# KeyBoard.net
KiCad netlist of a schematic drawn in EAGLE
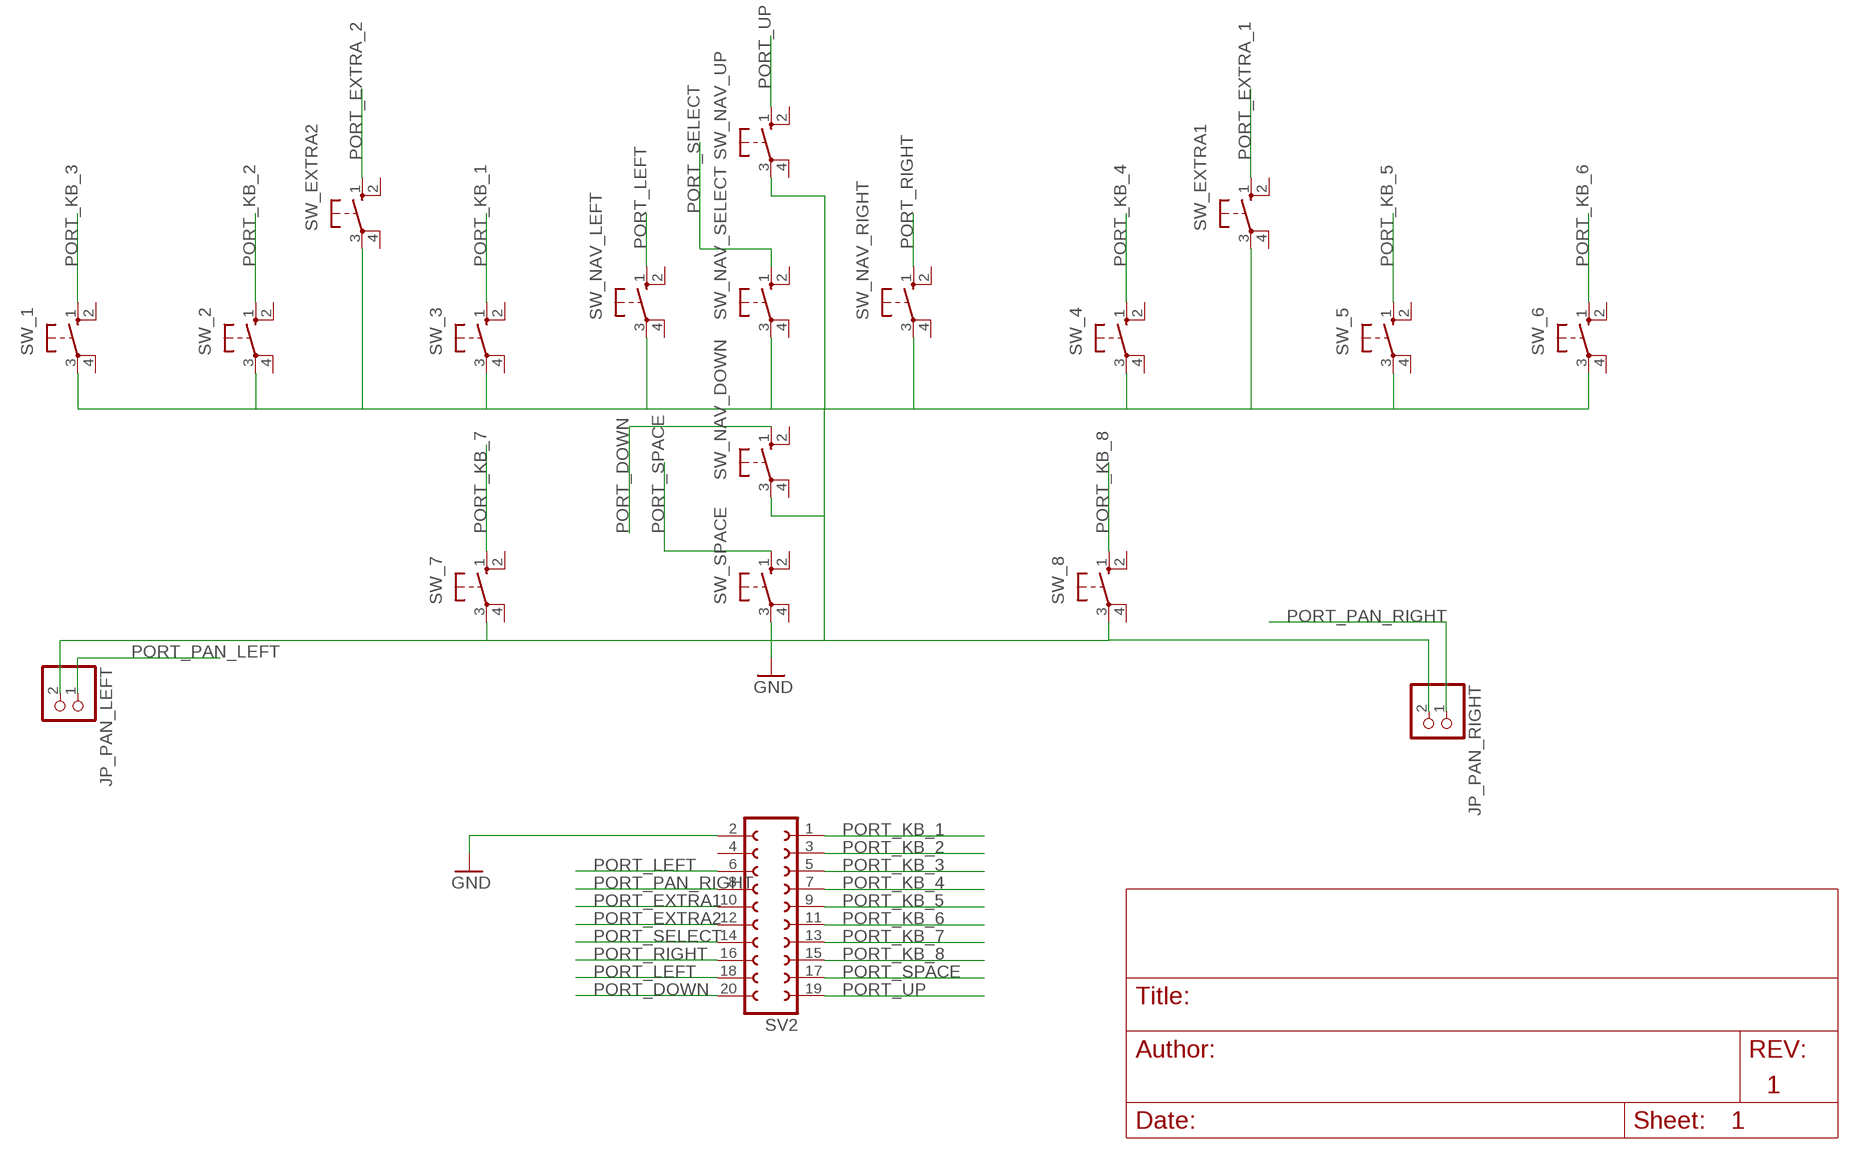
[diagram p0: schematic, sheet 1]

(export (version "E")
  (design (tool "Eeschema 10.0.6"))
  (components
    (comp (ref "JP_PAN_LEFT")
      (value "PINHD-1X2")
      (footprint "eagle-import:1X02")
      (libsource (lib "eagle-import") (part "PINHD-1X2"))
    )
    (comp (ref "JP_PAN_RIGHT")
      (value "PINHD-1X2")
      (footprint "eagle-import:1X02")
      (libsource (lib "eagle-import") (part "PINHD-1X2"))
    )
    (comp (ref "SV2")
      (value "FE10-2")
      (footprint "eagle-import:FE10-2")
      (libsource (lib "eagle-import") (part "FE10-2"))
    )
    (comp (ref "SW_1")
      (value "10-XX")
      (footprint "eagle-import:B3F-10XX")
      (fields (field (name "MPN") "B3F-1000"))
      (libsource (lib "eagle-import") (part "10-XX"))
    )
    (comp (ref "SW_2")
      (value "10-XX")
      (footprint "eagle-import:B3F-10XX")
      (fields (field (name "MPN") "B3F-1000"))
      (libsource (lib "eagle-import") (part "10-XX"))
    )
    (comp (ref "SW_3")
      (value "10-XX")
      (footprint "eagle-import:B3F-10XX")
      (fields (field (name "MPN") "B3F-1000"))
      (libsource (lib "eagle-import") (part "10-XX"))
    )
    (comp (ref "SW_4")
      (value "10-XX")
      (footprint "eagle-import:B3F-10XX")
      (fields (field (name "MPN") "B3F-1000"))
      (libsource (lib "eagle-import") (part "10-XX"))
    )
    (comp (ref "SW_5")
      (value "10-XX")
      (footprint "eagle-import:B3F-10XX")
      (fields (field (name "MPN") "B3F-1000"))
      (libsource (lib "eagle-import") (part "10-XX"))
    )
    (comp (ref "SW_6")
      (value "10-XX")
      (footprint "eagle-import:B3F-10XX")
      (fields (field (name "MPN") "B3F-1000"))
      (libsource (lib "eagle-import") (part "10-XX"))
    )
    (comp (ref "SW_7")
      (value "10-XX")
      (footprint "eagle-import:B3F-10XX")
      (fields (field (name "MPN") "B3F-1000"))
      (libsource (lib "eagle-import") (part "10-XX"))
    )
    (comp (ref "SW_8")
      (value "10-XX")
      (footprint "eagle-import:B3F-10XX")
      (fields (field (name "MPN") "B3F-1000"))
      (libsource (lib "eagle-import") (part "10-XX"))
    )
    (comp (ref "SW_EXTRA1")
      (value "10-XX")
      (footprint "eagle-import:B3F-10XX")
      (fields (field (name "MPN") "B3F-1000"))
      (libsource (lib "eagle-import") (part "10-XX"))
    )
    (comp (ref "SW_EXTRA2")
      (value "10-XX")
      (footprint "eagle-import:B3F-10XX")
      (fields (field (name "MPN") "B3F-1000"))
      (libsource (lib "eagle-import") (part "10-XX"))
    )
    (comp (ref "SW_NAV_DOWN")
      (value "10-XX")
      (footprint "eagle-import:B3F-10XX")
      (fields (field (name "MPN") "B3F-1000"))
      (libsource (lib "eagle-import") (part "10-XX"))
    )
    (comp (ref "SW_NAV_LEFT")
      (value "10-XX")
      (footprint "eagle-import:B3F-10XX")
      (fields (field (name "MPN") "B3F-1000"))
      (libsource (lib "eagle-import") (part "10-XX"))
    )
    (comp (ref "SW_NAV_RIGHT")
      (value "10-XX")
      (footprint "eagle-import:B3F-10XX")
      (fields (field (name "MPN") "B3F-1000"))
      (libsource (lib "eagle-import") (part "10-XX"))
    )
    (comp (ref "SW_NAV_SELECT")
      (value "10-XX")
      (footprint "eagle-import:B3F-10XX")
      (fields (field (name "MPN") "B3F-1000"))
      (libsource (lib "eagle-import") (part "10-XX"))
    )
    (comp (ref "SW_NAV_UP")
      (value "10-XX")
      (footprint "eagle-import:B3F-10XX")
      (fields (field (name "MPN") "B3F-1000"))
      (libsource (lib "eagle-import") (part "10-XX"))
    )
    (comp (ref "SW_SPACE")
      (value "10-XX")
      (footprint "eagle-import:B3F-10XX")
      (fields (field (name "MPN") "B3F-1000"))
      (libsource (lib "eagle-import") (part "10-XX"))
    )
  )
  (nets
    (net (code "1") (name "/PORT_DOWN") (class "Default")
      (node (ref "SV2") (pin "20") (pinfunction "20_20") (pintype "passive"))
      (node (ref "SW_NAV_DOWN") (pin "1") (pinfunction "S_1") (pintype "passive"))
    )
    (net (code "2") (name "/PORT_EXTRA1") (class "Default")
      (node (ref "SV2") (pin "10") (pinfunction "10_10") (pintype "passive"))
    )
    (net (code "3") (name "/PORT_EXTRA2") (class "Default")
      (node (ref "SV2") (pin "12") (pinfunction "12_12") (pintype "passive"))
    )
    (net (code "4") (name "/PORT_EXTRA_1") (class "Default")
      (node (ref "SW_EXTRA1") (pin "1") (pinfunction "S_1") (pintype "passive"))
    )
    (net (code "5") (name "/PORT_EXTRA_2") (class "Default")
      (node (ref "SW_EXTRA2") (pin "1") (pinfunction "S_1") (pintype "passive"))
    )
    (net (code "6") (name "/PORT_KB_1") (class "Default")
      (node (ref "SV2") (pin "1") (pinfunction "1_1") (pintype "passive"))
      (node (ref "SW_3") (pin "1") (pinfunction "S_1") (pintype "passive"))
    )
    (net (code "7") (name "/PORT_KB_2") (class "Default")
      (node (ref "SV2") (pin "3") (pinfunction "3_3") (pintype "passive"))
      (node (ref "SW_2") (pin "1") (pinfunction "S_1") (pintype "passive"))
    )
    (net (code "8") (name "/PORT_KB_3") (class "Default")
      (node (ref "SV2") (pin "5") (pinfunction "5_5") (pintype "passive"))
      (node (ref "SW_1") (pin "1") (pinfunction "S_1") (pintype "passive"))
    )
    (net (code "9") (name "/PORT_KB_4") (class "Default")
      (node (ref "SV2") (pin "7") (pinfunction "7_7") (pintype "passive"))
      (node (ref "SW_4") (pin "1") (pinfunction "S_1") (pintype "passive"))
    )
    (net (code "10") (name "/PORT_KB_5") (class "Default")
      (node (ref "SV2") (pin "9") (pinfunction "9_9") (pintype "passive"))
      (node (ref "SW_5") (pin "1") (pinfunction "S_1") (pintype "passive"))
    )
    (net (code "11") (name "/PORT_KB_6") (class "Default")
      (node (ref "SV2") (pin "11") (pinfunction "11_11") (pintype "passive"))
      (node (ref "SW_6") (pin "1") (pinfunction "S_1") (pintype "passive"))
    )
    (net (code "12") (name "/PORT_KB_7") (class "Default")
      (node (ref "SV2") (pin "13") (pinfunction "13_13") (pintype "passive"))
      (node (ref "SW_7") (pin "1") (pinfunction "S_1") (pintype "passive"))
    )
    (net (code "13") (name "/PORT_KB_8") (class "Default")
      (node (ref "SV2") (pin "15") (pinfunction "15_15") (pintype "passive"))
      (node (ref "SW_8") (pin "1") (pinfunction "S_1") (pintype "passive"))
    )
    (net (code "14") (name "/PORT_LEFT") (class "Default")
      (node (ref "SV2") (pin "18") (pinfunction "18_18") (pintype "passive"))
      (node (ref "SV2") (pin "6") (pinfunction "6_6") (pintype "passive"))
      (node (ref "SW_NAV_LEFT") (pin "1") (pinfunction "S_1") (pintype "passive"))
    )
    (net (code "15") (name "/PORT_PAN_LEFT") (class "Default")
      (node (ref "JP_PAN_LEFT") (pin "1") (pinfunction "1_1") (pintype "passive"))
    )
    (net (code "16") (name "/PORT_PAN_RIGHT") (class "Default")
      (node (ref "JP_PAN_RIGHT") (pin "1") (pinfunction "1_1") (pintype "passive"))
      (node (ref "SV2") (pin "8") (pinfunction "8_8") (pintype "passive"))
    )
    (net (code "17") (name "/PORT_RIGHT") (class "Default")
      (node (ref "SV2") (pin "16") (pinfunction "16_16") (pintype "passive"))
      (node (ref "SW_NAV_RIGHT") (pin "1") (pinfunction "S_1") (pintype "passive"))
    )
    (net (code "18") (name "/PORT_SELECT") (class "Default")
      (node (ref "SV2") (pin "14") (pinfunction "14_14") (pintype "passive"))
      (node (ref "SW_NAV_SELECT") (pin "1") (pinfunction "S_1") (pintype "passive"))
    )
    (net (code "19") (name "/PORT_SPACE") (class "Default")
      (node (ref "SV2") (pin "17") (pinfunction "17_17") (pintype "passive"))
      (node (ref "SW_SPACE") (pin "1") (pinfunction "S_1") (pintype "passive"))
    )
    (net (code "20") (name "/PORT_UP") (class "Default")
      (node (ref "SV2") (pin "19") (pinfunction "19_19") (pintype "passive"))
      (node (ref "SW_NAV_UP") (pin "1") (pinfunction "S_1") (pintype "passive"))
    )
    (net (code "21") (name "GND") (class "Default")
      (node (ref "JP_PAN_LEFT") (pin "2") (pinfunction "2_2") (pintype "passive"))
      (node (ref "JP_PAN_RIGHT") (pin "2") (pinfunction "2_2") (pintype "passive"))
      (node (ref "SV2") (pin "2") (pinfunction "2_2") (pintype "passive"))
      (node (ref "SW_1") (pin "3") (pinfunction "P_3") (pintype "passive"))
      (node (ref "SW_2") (pin "3") (pinfunction "P_3") (pintype "passive"))
      (node (ref "SW_3") (pin "3") (pinfunction "P_3") (pintype "passive"))
      (node (ref "SW_4") (pin "3") (pinfunction "P_3") (pintype "passive"))
      (node (ref "SW_5") (pin "3") (pinfunction "P_3") (pintype "passive"))
      (node (ref "SW_6") (pin "3") (pinfunction "P_3") (pintype "passive"))
      (node (ref "SW_7") (pin "3") (pinfunction "P_3") (pintype "passive"))
      (node (ref "SW_8") (pin "3") (pinfunction "P_3") (pintype "passive"))
      (node (ref "SW_EXTRA1") (pin "3") (pinfunction "P_3") (pintype "passive"))
      (node (ref "SW_EXTRA2") (pin "3") (pinfunction "P_3") (pintype "passive"))
      (node (ref "SW_NAV_DOWN") (pin "3") (pinfunction "P_3") (pintype "passive"))
      (node (ref "SW_NAV_LEFT") (pin "3") (pinfunction "P_3") (pintype "passive"))
      (node (ref "SW_NAV_RIGHT") (pin "3") (pinfunction "P_3") (pintype "passive"))
      (node (ref "SW_NAV_SELECT") (pin "3") (pinfunction "P_3") (pintype "passive"))
      (node (ref "SW_NAV_UP") (pin "3") (pinfunction "P_3") (pintype "passive"))
      (node (ref "SW_SPACE") (pin "3") (pinfunction "P_3") (pintype "passive"))
    )
    (net (code "22") (name "unconnected-(SV2-Pad4)") (class "Default")
      (node (ref "SV2") (pin "4") (pinfunction "4_4") (pintype "passive"))
    )
    (net (code "23") (name "unconnected-(SW_1-P1-Pad4)") (class "Default")
      (node (ref "SW_1") (pin "4") (pinfunction "P1_4") (pintype "passive"))
    )
    (net (code "24") (name "unconnected-(SW_1-S1-Pad2)") (class "Default")
      (node (ref "SW_1") (pin "2") (pinfunction "S1_2") (pintype "passive"))
    )
    (net (code "25") (name "unconnected-(SW_2-P1-Pad4)") (class "Default")
      (node (ref "SW_2") (pin "4") (pinfunction "P1_4") (pintype "passive"))
    )
    (net (code "26") (name "unconnected-(SW_2-S1-Pad2)") (class "Default")
      (node (ref "SW_2") (pin "2") (pinfunction "S1_2") (pintype "passive"))
    )
    (net (code "27") (name "unconnected-(SW_3-P1-Pad4)") (class "Default")
      (node (ref "SW_3") (pin "4") (pinfunction "P1_4") (pintype "passive"))
    )
    (net (code "28") (name "unconnected-(SW_3-S1-Pad2)") (class "Default")
      (node (ref "SW_3") (pin "2") (pinfunction "S1_2") (pintype "passive"))
    )
    (net (code "29") (name "unconnected-(SW_4-P1-Pad4)") (class "Default")
      (node (ref "SW_4") (pin "4") (pinfunction "P1_4") (pintype "passive"))
    )
    (net (code "30") (name "unconnected-(SW_4-S1-Pad2)") (class "Default")
      (node (ref "SW_4") (pin "2") (pinfunction "S1_2") (pintype "passive"))
    )
    (net (code "31") (name "unconnected-(SW_5-P1-Pad4)") (class "Default")
      (node (ref "SW_5") (pin "4") (pinfunction "P1_4") (pintype "passive"))
    )
    (net (code "32") (name "unconnected-(SW_5-S1-Pad2)") (class "Default")
      (node (ref "SW_5") (pin "2") (pinfunction "S1_2") (pintype "passive"))
    )
    (net (code "33") (name "unconnected-(SW_6-P1-Pad4)") (class "Default")
      (node (ref "SW_6") (pin "4") (pinfunction "P1_4") (pintype "passive"))
    )
    (net (code "34") (name "unconnected-(SW_6-S1-Pad2)") (class "Default")
      (node (ref "SW_6") (pin "2") (pinfunction "S1_2") (pintype "passive"))
    )
    (net (code "35") (name "unconnected-(SW_7-P1-Pad4)") (class "Default")
      (node (ref "SW_7") (pin "4") (pinfunction "P1_4") (pintype "passive"))
    )
    (net (code "36") (name "unconnected-(SW_7-S1-Pad2)") (class "Default")
      (node (ref "SW_7") (pin "2") (pinfunction "S1_2") (pintype "passive"))
    )
    (net (code "37") (name "unconnected-(SW_8-P1-Pad4)") (class "Default")
      (node (ref "SW_8") (pin "4") (pinfunction "P1_4") (pintype "passive"))
    )
    (net (code "38") (name "unconnected-(SW_8-S1-Pad2)") (class "Default")
      (node (ref "SW_8") (pin "2") (pinfunction "S1_2") (pintype "passive"))
    )
    (net (code "39") (name "unconnected-(SW_EXTRA1-P1-Pad4)") (class "Default")
      (node (ref "SW_EXTRA1") (pin "4") (pinfunction "P1_4") (pintype "passive"))
    )
    (net (code "40") (name "unconnected-(SW_EXTRA1-S1-Pad2)") (class "Default")
      (node (ref "SW_EXTRA1") (pin "2") (pinfunction "S1_2") (pintype "passive"))
    )
    (net (code "41") (name "unconnected-(SW_EXTRA2-P1-Pad4)") (class "Default")
      (node (ref "SW_EXTRA2") (pin "4") (pinfunction "P1_4") (pintype "passive"))
    )
    (net (code "42") (name "unconnected-(SW_EXTRA2-S1-Pad2)") (class "Default")
      (node (ref "SW_EXTRA2") (pin "2") (pinfunction "S1_2") (pintype "passive"))
    )
    (net (code "43") (name "unconnected-(SW_NAV_DOWN-P1-Pad4)") (class "Default")
      (node (ref "SW_NAV_DOWN") (pin "4") (pinfunction "P1_4") (pintype "passive"))
    )
    (net (code "44") (name "unconnected-(SW_NAV_DOWN-S1-Pad2)") (class "Default")
      (node (ref "SW_NAV_DOWN") (pin "2") (pinfunction "S1_2") (pintype "passive"))
    )
    (net (code "45") (name "unconnected-(SW_NAV_LEFT-P1-Pad4)") (class "Default")
      (node (ref "SW_NAV_LEFT") (pin "4") (pinfunction "P1_4") (pintype "passive"))
    )
    (net (code "46") (name "unconnected-(SW_NAV_LEFT-S1-Pad2)") (class "Default")
      (node (ref "SW_NAV_LEFT") (pin "2") (pinfunction "S1_2") (pintype "passive"))
    )
    (net (code "47") (name "unconnected-(SW_NAV_RIGHT-P1-Pad4)") (class "Default")
      (node (ref "SW_NAV_RIGHT") (pin "4") (pinfunction "P1_4") (pintype "passive"))
    )
    (net (code "48") (name "unconnected-(SW_NAV_RIGHT-S1-Pad2)") (class "Default")
      (node (ref "SW_NAV_RIGHT") (pin "2") (pinfunction "S1_2") (pintype "passive"))
    )
    (net (code "49") (name "unconnected-(SW_NAV_SELECT-P1-Pad4)") (class "Default")
      (node (ref "SW_NAV_SELECT") (pin "4") (pinfunction "P1_4") (pintype "passive"))
    )
    (net (code "50") (name "unconnected-(SW_NAV_SELECT-S1-Pad2)") (class "Default")
      (node (ref "SW_NAV_SELECT") (pin "2") (pinfunction "S1_2") (pintype "passive"))
    )
    (net (code "51") (name "unconnected-(SW_NAV_UP-P1-Pad4)") (class "Default")
      (node (ref "SW_NAV_UP") (pin "4") (pinfunction "P1_4") (pintype "passive"))
    )
    (net (code "52") (name "unconnected-(SW_NAV_UP-S1-Pad2)") (class "Default")
      (node (ref "SW_NAV_UP") (pin "2") (pinfunction "S1_2") (pintype "passive"))
    )
    (net (code "53") (name "unconnected-(SW_SPACE-P1-Pad4)") (class "Default")
      (node (ref "SW_SPACE") (pin "4") (pinfunction "P1_4") (pintype "passive"))
    )
    (net (code "54") (name "unconnected-(SW_SPACE-S1-Pad2)") (class "Default")
      (node (ref "SW_SPACE") (pin "2") (pinfunction "S1_2") (pintype "passive"))
    )
  )
)
